# Sheet1.net
KiCad netlist of a schematic drawn in Altium Designer
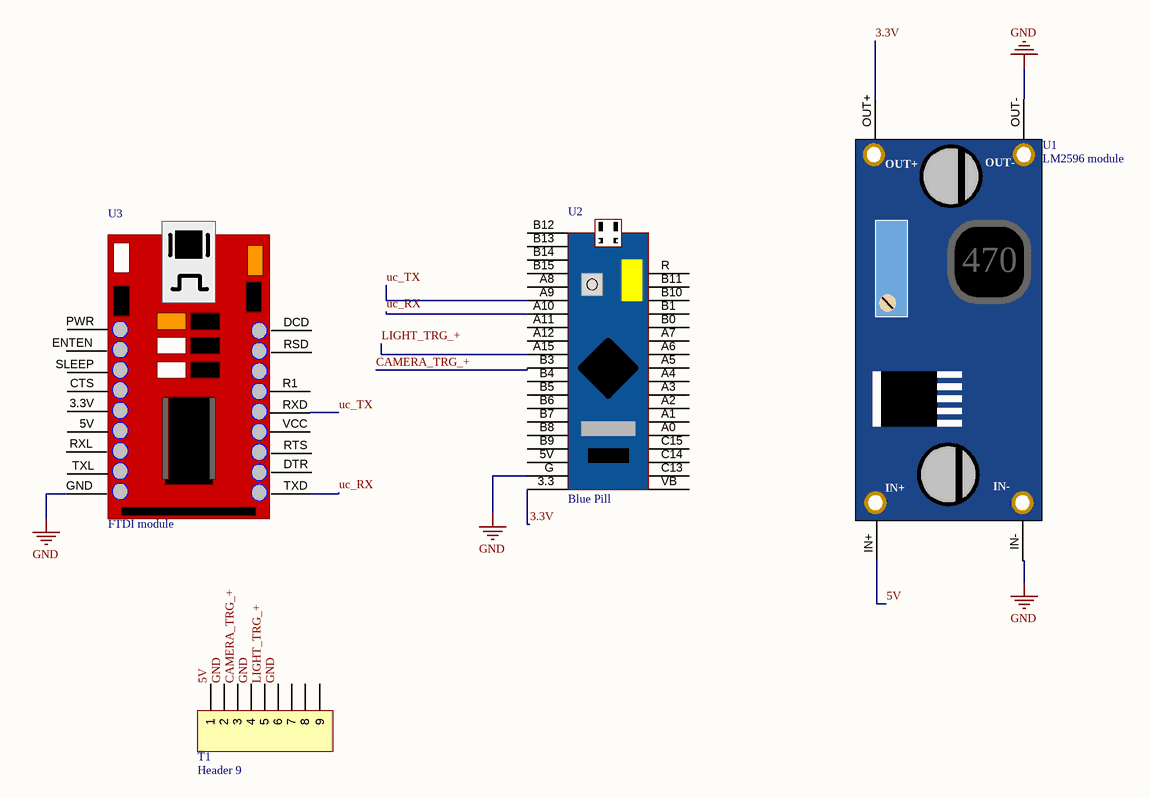
[diagram p0: Sheet1.SchDoc]

(export (version "E")
  (design (tool "Eeschema 10.0.6"))
  (components
    (comp (ref "T1")
      (value "Header 9")
      (footprint "1X09")
      (libsource (lib "Behyaar_CONNECTORS AND SOKET_v1") (part "Header 9"))
    )
    (comp (ref "U1")
      (value "LM2596 module")
      (footprint "LM2596 module")
      (libsource (lib "lm2596 module") (part "LM2596 module"))
    )
    (comp (ref "U2")
      (value "Blue Pill")
      (footprint "Blue Pill")
      (libsource (lib "Blue Pill") (part "Blue Pill"))
    )
    (comp (ref "U3")
      (value "FTDI module")
      (footprint "FTDI module")
      (libsource (lib "FTDI module") (part "FTDI module"))
    )
  )
  (nets
    (net (code "1") (name "/3.3V") (class "Default")
      (node (ref "U1") (pin "OUT+") (pinfunction "VB_OUT+") (pintype "passive"))
      (node (ref "U2") (pin "3.3") (pinfunction "20_3.3") (pintype "passive"))
    )
    (net (code "2") (name "/5V") (class "Default")
      (node (ref "T1") (pin "1") (pinfunction "1_1") (pintype "passive"))
      (node (ref "U1") (pin "IN+") (pinfunction "IN+_IN+") (pintype "passive"))
    )
    (net (code "3") (name "/CAMERA_TRG_+") (class "Default")
      (node (ref "T1") (pin "3") (pinfunction "3_3") (pintype "passive"))
      (node (ref "U2") (pin "B3") (pinfunction "11_B3") (pintype "passive"))
    )
    (net (code "4") (name "/LIGHT_TRG_+") (class "Default")
      (node (ref "T1") (pin "5") (pinfunction "5_5") (pintype "passive"))
      (node (ref "U2") (pin "A15") (pinfunction "10_A15") (pintype "passive"))
    )
    (net (code "5") (name "/uc_RX") (class "Default")
      (node (ref "U2") (pin "A10") (pinfunction "7_A10") (pintype "passive"))
      (node (ref "U3") (pin "TXD") (pinfunction "TXD_TXD") (pintype "passive"))
    )
    (net (code "6") (name "/uc_TX") (class "Default")
      (node (ref "U2") (pin "A9") (pinfunction "A9_A9") (pintype "passive"))
      (node (ref "U3") (pin "RXD") (pinfunction "RXD_RXD") (pintype "passive"))
    )
    (net (code "7") (name "GND") (class "Default")
      (node (ref "T1") (pin "2") (pinfunction "2_2") (pintype "passive"))
      (node (ref "T1") (pin "4") (pinfunction "4_4") (pintype "passive"))
      (node (ref "T1") (pin "6") (pinfunction "6_6") (pintype "passive"))
      (node (ref "U1") (pin "IN-") (pinfunction "IN-_IN-") (pintype "passive"))
      (node (ref "U1") (pin "OUT-") (pinfunction "OUT-_OUT-") (pintype "passive"))
      (node (ref "U2") (pin "G") (pinfunction "19_G") (pintype "passive"))
      (node (ref "U3") (pin "GND") (pinfunction "GND_GND") (pintype "passive"))
    )
    (net (code "8") (name "unconnected-(T1-Pad7)") (class "Default")
      (node (ref "T1") (pin "7") (pinfunction "7_7") (pintype "passive"))
    )
    (net (code "9") (name "unconnected-(T1-Pad8)") (class "Default")
      (node (ref "T1") (pin "8") (pinfunction "8_8") (pintype "passive"))
    )
    (net (code "10") (name "unconnected-(T1-Pad9)") (class "Default")
      (node (ref "T1") (pin "9") (pinfunction "9_9") (pintype "passive"))
    )
    (net (code "11") (name "unconnected-(U2-8-PadA11)") (class "Default")
      (node (ref "U2") (pin "A11") (pinfunction "8_A11") (pintype "passive"))
    )
    (net (code "12") (name "unconnected-(U2-9-PadA12)") (class "Default")
      (node (ref "U2") (pin "A12") (pinfunction "9_A12") (pintype "passive"))
    )
    (net (code "13") (name "unconnected-(U2-12-PadB4)") (class "Default")
      (node (ref "U2") (pin "B4") (pinfunction "12_B4") (pintype "passive"))
    )
    (net (code "14") (name "unconnected-(U2-13-PadB5)") (class "Default")
      (node (ref "U2") (pin "B5") (pinfunction "13_B5") (pintype "passive"))
    )
    (net (code "15") (name "unconnected-(U2-14-PadB6)") (class "Default")
      (node (ref "U2") (pin "B6") (pinfunction "14_B6") (pintype "passive"))
    )
    (net (code "16") (name "unconnected-(U2-15-PadB7)") (class "Default")
      (node (ref "U2") (pin "B7") (pinfunction "15_B7") (pintype "passive"))
    )
    (net (code "17") (name "unconnected-(U2-16-PadB8)") (class "Default")
      (node (ref "U2") (pin "B8") (pinfunction "16_B8") (pintype "passive"))
    )
    (net (code "18") (name "unconnected-(U2-17-PadB9)") (class "Default")
      (node (ref "U2") (pin "B9") (pinfunction "17_B9") (pintype "passive"))
    )
    (net (code "19") (name "unconnected-(U2-18-Pad5V)") (class "Default")
      (node (ref "U2") (pin "5V") (pinfunction "18_5V") (pintype "passive"))
    )
    (net (code "20") (name "unconnected-(U2-21-PadVB)") (class "Default")
      (node (ref "U2") (pin "VB") (pinfunction "21_VB") (pintype "passive"))
    )
    (net (code "21") (name "unconnected-(U2-22-PadC13)") (class "Default")
      (node (ref "U2") (pin "C13") (pinfunction "22_C13") (pintype "passive"))
    )
    (net (code "22") (name "unconnected-(U2-23-PadC14)") (class "Default")
      (node (ref "U2") (pin "C14") (pinfunction "23_C14") (pintype "passive"))
    )
    (net (code "23") (name "unconnected-(U2-24-PadC15)") (class "Default")
      (node (ref "U2") (pin "C15") (pinfunction "24_C15") (pintype "passive"))
    )
    (net (code "24") (name "unconnected-(U2-25-PadA0)") (class "Default")
      (node (ref "U2") (pin "A0") (pinfunction "25_A0") (pintype "passive"))
    )
    (net (code "25") (name "unconnected-(U2-26-PadA1)") (class "Default")
      (node (ref "U2") (pin "A1") (pinfunction "26_A1") (pintype "passive"))
    )
    (net (code "26") (name "unconnected-(U2-27-PadA2)") (class "Default")
      (node (ref "U2") (pin "A2") (pinfunction "27_A2") (pintype "passive"))
    )
    (net (code "27") (name "unconnected-(U2-28-PadA3)") (class "Default")
      (node (ref "U2") (pin "A3") (pinfunction "28_A3") (pintype "passive"))
    )
    (net (code "28") (name "unconnected-(U2-29-PadA4)") (class "Default")
      (node (ref "U2") (pin "A4") (pinfunction "29_A4") (pintype "passive"))
    )
    (net (code "29") (name "unconnected-(U2-30-PadA5)") (class "Default")
      (node (ref "U2") (pin "A5") (pinfunction "30_A5") (pintype "passive"))
    )
    (net (code "30") (name "unconnected-(U2-31-PadA6)") (class "Default")
      (node (ref "U2") (pin "A6") (pinfunction "31_A6") (pintype "passive"))
    )
    (net (code "31") (name "unconnected-(U2-32-PadA7)") (class "Default")
      (node (ref "U2") (pin "A7") (pinfunction "32_A7") (pintype "passive"))
    )
    (net (code "32") (name "unconnected-(U2-33-PadB0)") (class "Default")
      (node (ref "U2") (pin "B0") (pinfunction "33_B0") (pintype "passive"))
    )
    (net (code "33") (name "unconnected-(U2-34-PadB1)") (class "Default")
      (node (ref "U2") (pin "B1") (pinfunction "34_B1") (pintype "passive"))
    )
    (net (code "34") (name "unconnected-(U2-35-PadB10)") (class "Default")
      (node (ref "U2") (pin "B10") (pinfunction "35_B10") (pintype "passive"))
    )
    (net (code "35") (name "unconnected-(U2-36-PadB11)") (class "Default")
      (node (ref "U2") (pin "B11") (pinfunction "36_B11") (pintype "passive"))
    )
    (net (code "36") (name "unconnected-(U2-37-PadR)") (class "Default")
      (node (ref "U2") (pin "R") (pinfunction "37_R") (pintype "passive"))
    )
    (net (code "37") (name "unconnected-(U2-PadA8)") (class "Default")
      (node (ref "U2") (pin "A8") (pinfunction "A8_A8") (pintype "passive"))
    )
    (net (code "38") (name "unconnected-(U2-PadB12)") (class "Default")
      (node (ref "U2") (pin "B12") (pinfunction "B12_B12") (pintype "passive"))
    )
    (net (code "39") (name "unconnected-(U2-PadB13)") (class "Default")
      (node (ref "U2") (pin "B13") (pinfunction "B13_B13") (pintype "passive"))
    )
    (net (code "40") (name "unconnected-(U2-PadB14)") (class "Default")
      (node (ref "U2") (pin "B14") (pinfunction "B14_B14") (pintype "passive"))
    )
    (net (code "41") (name "unconnected-(U2-PadB15)") (class "Default")
      (node (ref "U2") (pin "B15") (pinfunction "B15_B15") (pintype "passive"))
    )
    (net (code "42") (name "unconnected-(U3-Pad3.3V)") (class "Default")
      (node (ref "U3") (pin "3.3V") (pinfunction "3.3V_3.3V") (pintype "passive"))
    )
    (net (code "43") (name "unconnected-(U3-Pad5V)") (class "Default")
      (node (ref "U3") (pin "5V") (pinfunction "5V_5V") (pintype "passive"))
    )
    (net (code "44") (name "unconnected-(U3-PadCTS)") (class "Default")
      (node (ref "U3") (pin "CTS") (pinfunction "CTS_CTS") (pintype "passive"))
    )
    (net (code "45") (name "unconnected-(U3-PadDCD)") (class "Default")
      (node (ref "U3") (pin "DCD") (pinfunction "DCD_DCD") (pintype "passive"))
    )
    (net (code "46") (name "unconnected-(U3-PadDTR)") (class "Default")
      (node (ref "U3") (pin "DTR") (pinfunction "DTR_DTR") (pintype "passive"))
    )
    (net (code "47") (name "unconnected-(U3-PadENTEN)") (class "Default")
      (node (ref "U3") (pin "ENTEN") (pinfunction "ENTEN_ENTEN") (pintype "passive"))
    )
    (net (code "48") (name "unconnected-(U3-PadPWR)") (class "Default")
      (node (ref "U3") (pin "PWR") (pinfunction "PWR_PWR") (pintype "passive"))
    )
    (net (code "49") (name "unconnected-(U3-PadR1)") (class "Default")
      (node (ref "U3") (pin "R1") (pinfunction "R1_R1") (pintype "passive"))
    )
    (net (code "50") (name "unconnected-(U3-PadRSD)") (class "Default")
      (node (ref "U3") (pin "RSD") (pinfunction "RSD_RSD") (pintype "passive"))
    )
    (net (code "51") (name "unconnected-(U3-PadRTS)") (class "Default")
      (node (ref "U3") (pin "RTS") (pinfunction "RTS_RTS") (pintype "passive"))
    )
    (net (code "52") (name "unconnected-(U3-PadRXL)") (class "Default")
      (node (ref "U3") (pin "RXL") (pinfunction "RXL_RXL") (pintype "passive"))
    )
    (net (code "53") (name "unconnected-(U3-PadSLEEP)") (class "Default")
      (node (ref "U3") (pin "SLEEP") (pinfunction "SLEEP_SLEEP") (pintype "passive"))
    )
    (net (code "54") (name "unconnected-(U3-PadTXL)") (class "Default")
      (node (ref "U3") (pin "TXL") (pinfunction "TXL_TXL") (pintype "passive"))
    )
    (net (code "55") (name "unconnected-(U3-PadVCC)") (class "Default")
      (node (ref "U3") (pin "VCC") (pinfunction "VCC_VCC") (pintype "passive"))
    )
  )
)
